# BeetleMeterV2.net
KiCad netlist of a schematic drawn in Altium Designer
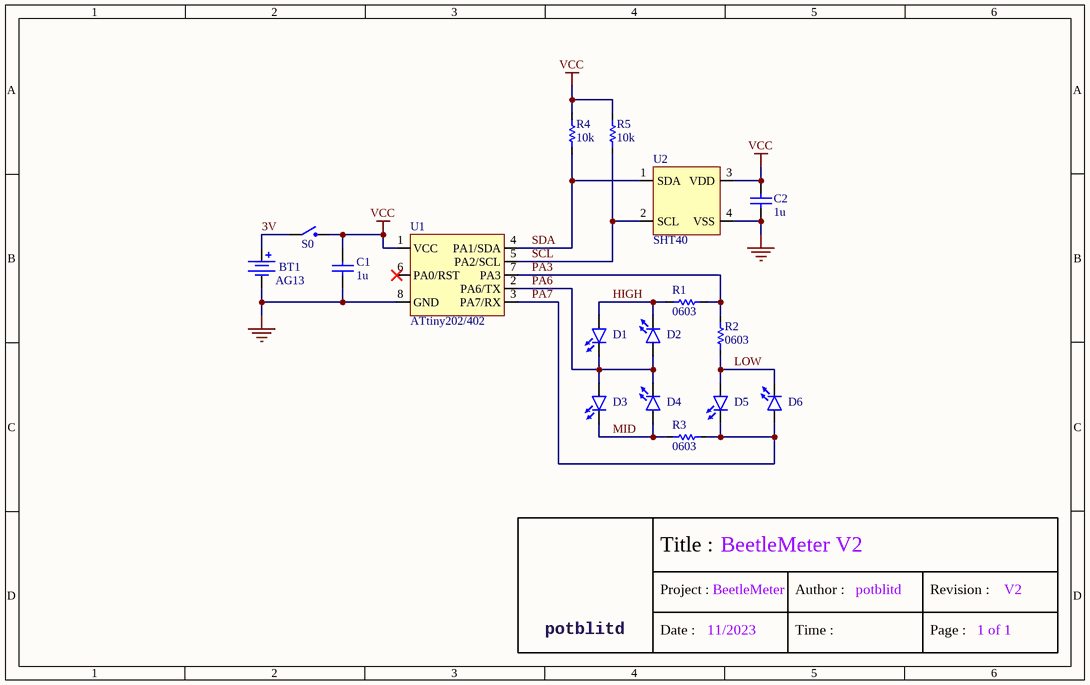
[diagram p0: BeetleMeterV2.SchDoc]

(export (version "E")
  (design (tool "Eeschema 10.0.6"))
  (components
    (comp (ref "BT1")
      (value "AG13")
      (footprint "AG13")
      (description "Coin cell battery 3V")
      (libsource (lib "AltiumLib") (part "Battery 3V"))
    )
    (comp (ref "C1")
      (value "Capacitor")
      (footprint "0603C")
      (description "Capacitor 1uF")
      (fields (field (name "ALTIUM_VALUE") "1u"))
      (libsource (lib "Simulation Generic Components") (part "Capacitor"))
    )
    (comp (ref "C2")
      (value "1u")
      (footprint "0603C")
      (description "Capacitor 1uF")
      (fields (field (name "Comment") "Capacitor"))
      (libsource (lib "Simulation Generic Components") (part "Capacitor"))
    )
    (comp (ref "D1")
      (value "LED")
      (footprint "0603D")
      (description "General LED symbol")
      (libsource (lib "AltiumLib") (part "LED"))
    )
    (comp (ref "D2")
      (value "LED")
      (footprint "0603D")
      (description "General LED symbol")
      (libsource (lib "AltiumLib") (part "LED"))
    )
    (comp (ref "D3")
      (value "LED")
      (footprint "0603D")
      (description "General LED symbol")
      (libsource (lib "AltiumLib") (part "LED"))
    )
    (comp (ref "D4")
      (value "LED")
      (footprint "0603D")
      (description "General LED symbol")
      (libsource (lib "AltiumLib") (part "LED"))
    )
    (comp (ref "D5")
      (value "LED")
      (footprint "0603D")
      (description "General LED symbol")
      (libsource (lib "AltiumLib") (part "LED"))
    )
    (comp (ref "D6")
      (value "LED")
      (footprint "0603D")
      (description "General LED symbol")
      (libsource (lib "AltiumLib") (part "LED"))
    )
    (comp (ref "R1")
      (value "0603")
      (footprint "0603R")
      (description "Resistor")
      (libsource (lib "AltiumLib") (part "RES"))
    )
    (comp (ref "R2")
      (value "0603")
      (footprint "0603R")
      (description "Resistor")
      (libsource (lib "AltiumLib") (part "RES"))
    )
    (comp (ref "R3")
      (value "0603")
      (footprint "0603R")
      (description "Resistor")
      (libsource (lib "AltiumLib") (part "RES"))
    )
    (comp (ref "R4")
      (value "10k")
      (footprint "0603R")
      (description "Resistor")
      (libsource (lib "AltiumLib") (part "RES"))
    )
    (comp (ref "R5")
      (value "10k")
      (footprint "0603R")
      (description "Resistor")
      (libsource (lib "AltiumLib") (part "RES"))
    )
    (comp (ref "S0")
      (value "Switch")
      (footprint "SW_4.5*4.5")
      (description "2-positions switch open-closed")
      (libsource (lib "AltiumLib") (part "Switch-2"))
    )
    (comp (ref "U1")
      (value "ATtiny202/402")
      (footprint "SOP-8")
      (description "tiny AVR 8-pin microcontroller")
      (libsource (lib "AltiumLib") (part "ATtiny202/402"))
    )
    (comp (ref "U2")
      (value "SHT40")
      (footprint "DFN-4-EP(1.5x1.5)")
      (description "SHT40 temperature and humidity sensor")
      (libsource (lib "AltiumLib") (part "SHT40"))
    )
  )
  (nets
    (net (code "1") (name "/3V") (class "Default")
      (node (ref "BT1") (pin "1") (pinfunction "+_1") (pintype "passive"))
      (node (ref "S0") (pin "1") (pinfunction "1_1") (pintype "passive"))
    )
    (net (code "2") (name "/HIGH") (class "Default")
      (node (ref "D1") (pin "1") (pintype "passive"))
      (node (ref "D2") (pin "2") (pintype "passive"))
      (node (ref "R1") (pin "1") (pinfunction "1_1") (pintype "passive"))
    )
    (net (code "3") (name "/LOW") (class "Default")
      (node (ref "D5") (pin "1") (pintype "passive"))
      (node (ref "D6") (pin "2") (pintype "passive"))
      (node (ref "R2") (pin "1") (pinfunction "1_1") (pintype "passive"))
    )
    (net (code "4") (name "/MID") (class "Default")
      (node (ref "D3") (pin "2") (pintype "passive"))
      (node (ref "D4") (pin "1") (pintype "passive"))
      (node (ref "R3") (pin "2") (pinfunction "2_2") (pintype "passive"))
    )
    (net (code "5") (name "/PA3") (class "Default")
      (node (ref "R1") (pin "2") (pinfunction "2_2") (pintype "passive"))
      (node (ref "R2") (pin "2") (pinfunction "2_2") (pintype "passive"))
      (node (ref "U1") (pin "7") (pinfunction "PA3_7") (pintype "passive"))
    )
    (net (code "6") (name "/PA6") (class "Default")
      (node (ref "D1") (pin "2") (pintype "passive"))
      (node (ref "D2") (pin "1") (pintype "passive"))
      (node (ref "D3") (pin "1") (pintype "passive"))
      (node (ref "D4") (pin "2") (pintype "passive"))
      (node (ref "U1") (pin "2") (pinfunction "PA6/TX_2") (pintype "passive"))
    )
    (net (code "7") (name "/PA7") (class "Default")
      (node (ref "D5") (pin "2") (pintype "passive"))
      (node (ref "D6") (pin "1") (pintype "passive"))
      (node (ref "R3") (pin "1") (pinfunction "1_1") (pintype "passive"))
      (node (ref "U1") (pin "3") (pinfunction "PA7/RX_3") (pintype "passive"))
    )
    (net (code "8") (name "/SCL") (class "Default")
      (node (ref "R5") (pin "1") (pinfunction "1_1") (pintype "passive"))
      (node (ref "U1") (pin "5") (pinfunction "PA2/SCL_5") (pintype "passive"))
      (node (ref "U2") (pin "2") (pinfunction "SCL_2") (pintype "passive"))
    )
    (net (code "9") (name "/SDA") (class "Default")
      (node (ref "R4") (pin "1") (pinfunction "1_1") (pintype "passive"))
      (node (ref "U1") (pin "4") (pinfunction "PA1/SDA_4") (pintype "passive"))
      (node (ref "U2") (pin "1") (pinfunction "SDA_1") (pintype "passive"))
    )
    (net (code "10") (name "GND") (class "Default")
      (node (ref "BT1") (pin "2") (pinfunction "-_2") (pintype "passive"))
      (node (ref "C1") (pin "1") (pinfunction "1_1") (pintype "passive"))
      (node (ref "C2") (pin "2") (pinfunction "2_2") (pintype "passive"))
      (node (ref "U1") (pin "8") (pinfunction "GND_8") (pintype "passive"))
      (node (ref "U2") (pin "4") (pinfunction "VSS_4") (pintype "passive"))
    )
    (net (code "11") (name "VCC") (class "Default")
      (node (ref "C1") (pin "2") (pinfunction "2_2") (pintype "passive"))
      (node (ref "C2") (pin "1") (pinfunction "1_1") (pintype "passive"))
      (node (ref "R4") (pin "2") (pinfunction "2_2") (pintype "passive"))
      (node (ref "R5") (pin "2") (pinfunction "2_2") (pintype "passive"))
      (node (ref "S0") (pin "2") (pinfunction "2_2") (pintype "passive"))
      (node (ref "U1") (pin "1") (pinfunction "VCC_1") (pintype "passive"))
      (node (ref "U2") (pin "3") (pinfunction "VDD_3") (pintype "passive"))
    )
    (net (code "12") (name "unconnected-(U1-PA0{slash}RST-Pad6)") (class "Default")
      (node (ref "U1") (pin "6") (pinfunction "PA0/RST_6") (pintype "passive+no_connect"))
    )
  )
)
